# montaj_lora.net
KiCad netlist of a schematic drawn in EAGLE
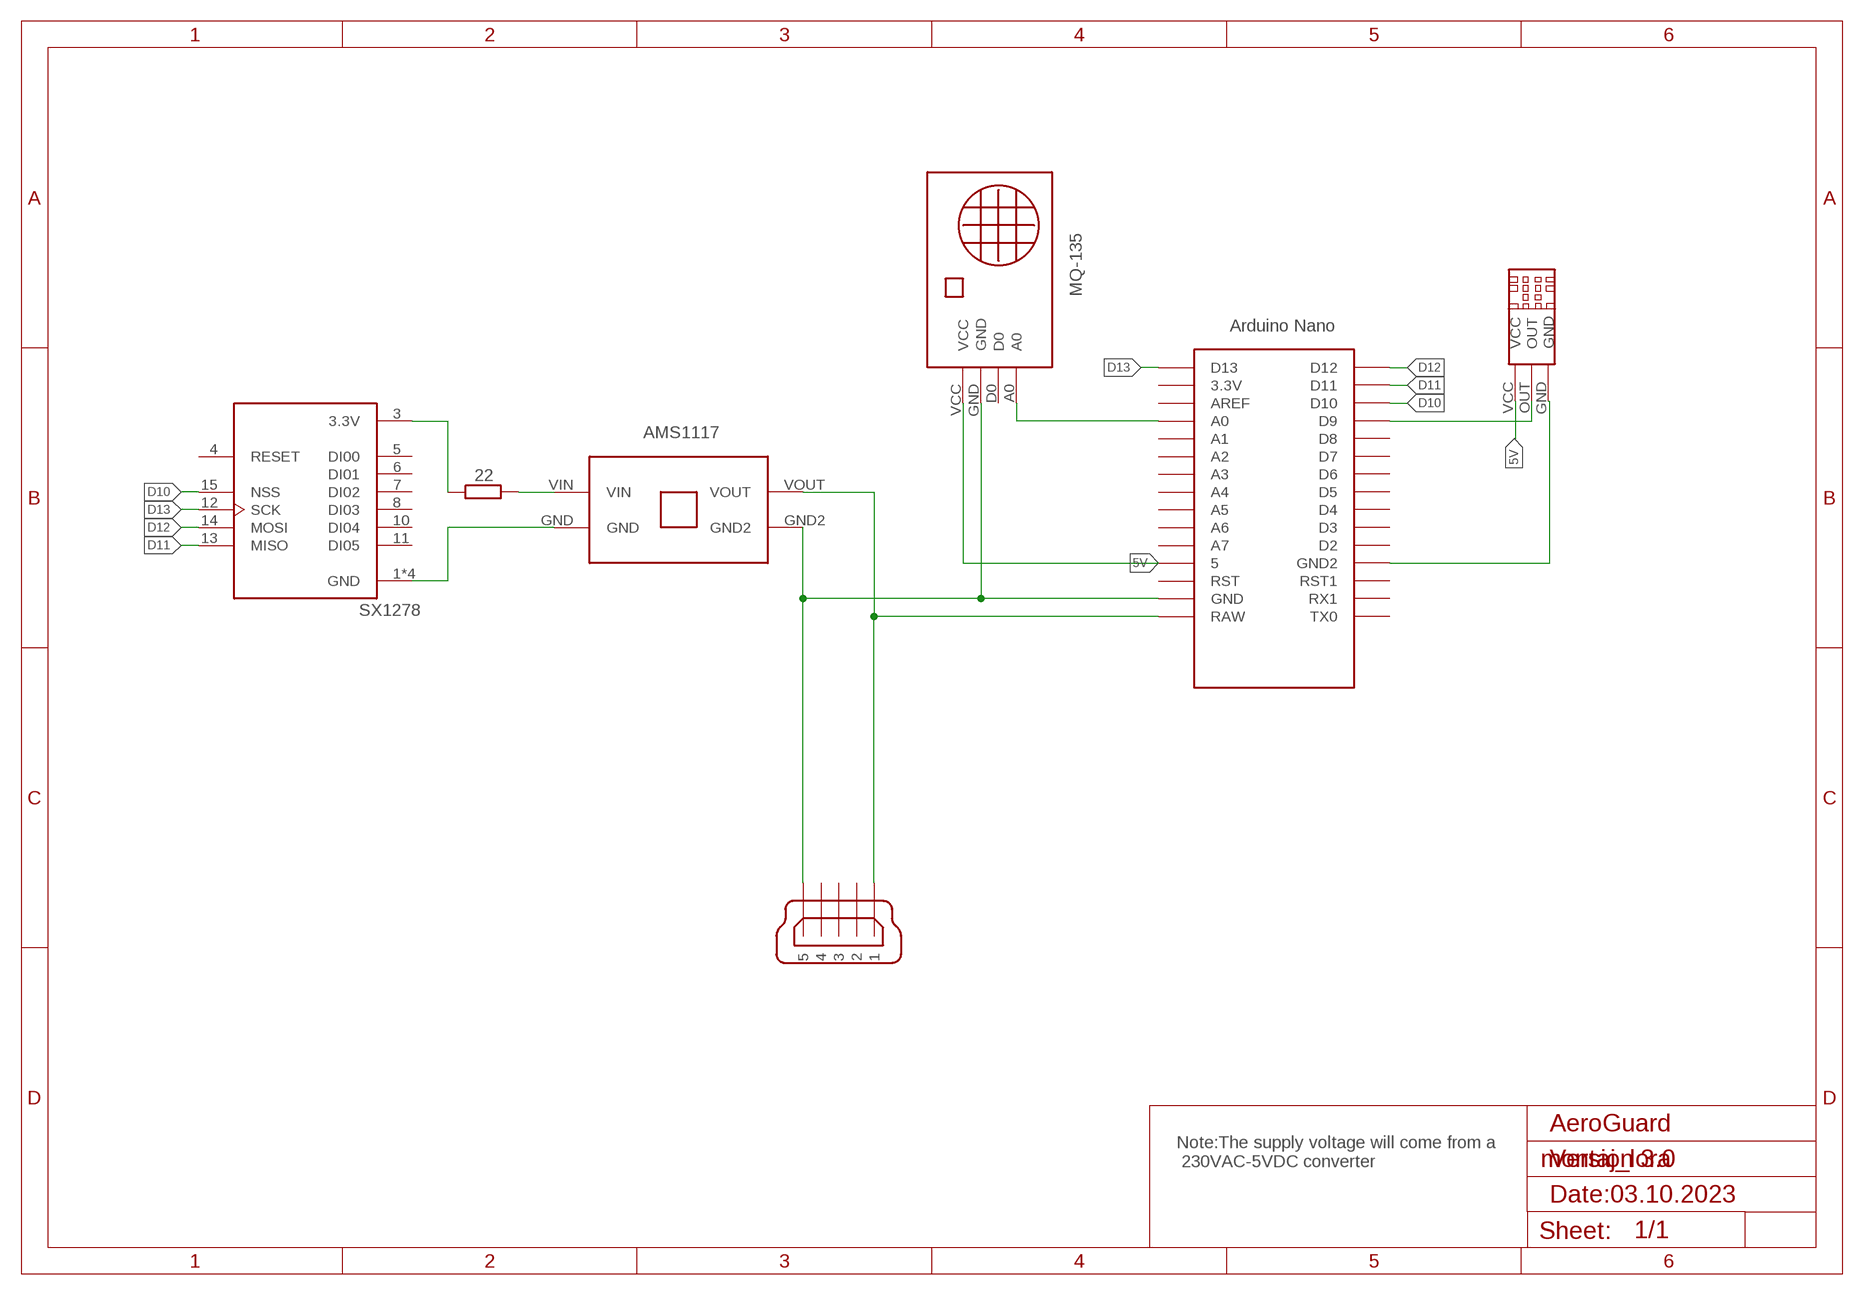
[diagram p0: schematic, sheet 1]

(export (version "E")
  (design (tool "Eeschema 10.0.6"))
  (components
    (comp (ref "22")
      (value "R-EU_0207/12")
      (footprint "eagle-import:0207_12")
      (libsource (lib "eagle-import") (part "R-EU_0207/12"))
    )
    (comp (ref "U$1")
      (value "NANO")
      (footprint "eagle-import:NANO")
      (libsource (lib "eagle-import") (part "NANO"))
    )
    (comp (ref "U$2")
      (value "DEV")
      (footprint "eagle-import:FOOT")
      (libsource (lib "eagle-import") (part "DEV"))
    )
    (comp (ref "U$3")
      (value "AMS1117")
      (footprint "eagle-import:AMS1117")
      (libsource (lib "eagle-import") (part "AMS1117"))
    )
    (comp (ref "U$4")
      (value "DHT11")
      (footprint "eagle-import:DHT11")
      (libsource (lib "eagle-import") (part "DHT11"))
    )
    (comp (ref "U1")
      (value "RA-02_LORA")
      (footprint "eagle-import:MODULE_RA-02_LORA")
      (fields (field (name "MF") "AI-Thinker") (field (name "MP") "Ra-02 LoRa"))
      (libsource (lib "eagle-import") (part "RA-02_LORA"))
    )
    (comp (ref "X1")
      (value "MINI-USB-SHIELD-UX60-MB-5S8")
      (footprint "eagle-import:UX60-MB-5S8")
      (libsource (lib "eagle-import") (part "MINI-USB-SHIELD-UX60-MB-5S8"))
    )
  )
  (nets
    (net (code "1") (name "5V") (class "Default")
      (node (ref "U$1") (pin "5V") (pinfunction "5_5V") (pintype "bidirectional"))
      (node (ref "U$2") (pin "VCC") (pinfunction "VCC_VCC") (pintype "bidirectional"))
    )
    (net (code "2") (name "D10") (class "Default")
      (node (ref "U$1") (pin "D10") (pinfunction "D10_D10") (pintype "bidirectional"))
      (node (ref "U1") (pin "15") (pinfunction "NSS_15") (pintype "input"))
    )
    (net (code "3") (name "D11") (class "Default")
      (node (ref "U$1") (pin "D11") (pinfunction "D11_D11") (pintype "bidirectional"))
      (node (ref "U1") (pin "13") (pinfunction "MISO_13") (pintype "output"))
    )
    (net (code "4") (name "D12") (class "Default")
      (node (ref "U$1") (pin "D12") (pinfunction "D12_D12") (pintype "bidirectional"))
      (node (ref "U1") (pin "14") (pinfunction "MOSI_14") (pintype "input"))
    )
    (net (code "5") (name "D13") (class "Default")
      (node (ref "U$1") (pin "D13") (pinfunction "D13_D13") (pintype "bidirectional"))
      (node (ref "U1") (pin "12") (pinfunction "SCK_12") (pintype "input"))
    )
    (net (code "6") (name "Net-(22-Pad2)") (class "Default")
      (node (ref "22") (pin "2") (pinfunction "2_2") (pintype "passive"))
      (node (ref "U$3") (pin "VIN") (pinfunction "VIN_VIN") (pintype "bidirectional"))
    )
    (net (code "7") (name "Net-(U$1-GND2)") (class "Default")
      (node (ref "U$1") (pin "GND1") (pinfunction "GND2_GND1") (pintype "bidirectional"))
      (node (ref "U$4") (pin "GND") (pinfunction "GND_GND") (pintype "bidirectional"))
    )
    (net (code "8") (name "Net-(U$1-PadA0)") (class "Default")
      (node (ref "U$1") (pin "A0") (pinfunction "A0_A0") (pintype "bidirectional"))
      (node (ref "U$2") (pin "A0") (pinfunction "A0_A0") (pintype "bidirectional"))
    )
    (net (code "9") (name "Net-(U$1-PadD9)") (class "Default")
      (node (ref "U$1") (pin "D9") (pinfunction "D9_D9") (pintype "bidirectional"))
      (node (ref "U$4") (pin "OUT") (pinfunction "OUT_OUT") (pintype "bidirectional"))
    )
    (net (code "10") (name "Net-(U$1-PadGND)") (class "Default")
      (node (ref "U$1") (pin "GND") (pinfunction "GND_GND") (pintype "bidirectional"))
      (node (ref "U$2") (pin "GND") (pinfunction "GND_GND") (pintype "bidirectional"))
      (node (ref "U$3") (pin "GND2") (pinfunction "GND2_GND2") (pintype "bidirectional"))
      (node (ref "X1") (pin "5") (pinfunction "5_5") (pintype "input"))
    )
    (net (code "11") (name "Net-(U$1-PadRAW)") (class "Default")
      (node (ref "U$1") (pin "RAW") (pinfunction "RAW_RAW") (pintype "bidirectional"))
      (node (ref "U$3") (pin "VOUT") (pinfunction "VOUT_VOUT") (pintype "bidirectional"))
      (node (ref "X1") (pin "1") (pinfunction "1_1") (pintype "input"))
    )
    (net (code "12") (name "Net-(U$3-PadGND)") (class "Default")
      (node (ref "U$3") (pin "GND") (pinfunction "GND_GND") (pintype "bidirectional"))
      (node (ref "U1") (pin "1") (pinfunction "GND_1") (pintype "power_in"))
      (node (ref "U1") (pin "16") (pinfunction "GND_16") (pintype "power_in"))
      (node (ref "U1") (pin "2") (pinfunction "GND_2") (pintype "power_in"))
      (node (ref "U1") (pin "9") (pinfunction "GND_9") (pintype "power_in"))
    )
    (net (code "13") (name "Net-(U1-3.3V)") (class "Default")
      (node (ref "22") (pin "1") (pinfunction "1_1") (pintype "passive"))
      (node (ref "U1") (pin "3") (pinfunction "3.3V_3") (pintype "power_in"))
    )
    (net (code "14") (name "unconnected-(U$1-Pad3.3V)") (class "Default")
      (node (ref "U$1") (pin "3.3V") (pinfunction "3.3V_3.3V") (pintype "bidirectional"))
    )
    (net (code "15") (name "unconnected-(U$1-PadA1)") (class "Default")
      (node (ref "U$1") (pin "A1") (pinfunction "A1_A1") (pintype "bidirectional"))
    )
    (net (code "16") (name "unconnected-(U$1-PadA2)") (class "Default")
      (node (ref "U$1") (pin "A2") (pinfunction "A2_A2") (pintype "bidirectional"))
    )
    (net (code "17") (name "unconnected-(U$1-PadA3)") (class "Default")
      (node (ref "U$1") (pin "A3") (pinfunction "A3_A3") (pintype "bidirectional"))
    )
    (net (code "18") (name "unconnected-(U$1-PadA4)") (class "Default")
      (node (ref "U$1") (pin "A4") (pinfunction "A4_A4") (pintype "bidirectional"))
    )
    (net (code "19") (name "unconnected-(U$1-PadA5)") (class "Default")
      (node (ref "U$1") (pin "A5") (pinfunction "A5_A5") (pintype "bidirectional"))
    )
    (net (code "20") (name "unconnected-(U$1-PadA6)") (class "Default")
      (node (ref "U$1") (pin "A6") (pinfunction "A6_A6") (pintype "bidirectional"))
    )
    (net (code "21") (name "unconnected-(U$1-PadA7)") (class "Default")
      (node (ref "U$1") (pin "A7") (pinfunction "A7_A7") (pintype "bidirectional"))
    )
    (net (code "22") (name "unconnected-(U$1-PadAREF)") (class "Default")
      (node (ref "U$1") (pin "AREF") (pinfunction "AREF_AREF") (pintype "bidirectional"))
    )
    (net (code "23") (name "unconnected-(U$1-PadD2)") (class "Default")
      (node (ref "U$1") (pin "D2") (pinfunction "D2_D2") (pintype "bidirectional"))
    )
    (net (code "24") (name "unconnected-(U$1-PadD3)") (class "Default")
      (node (ref "U$1") (pin "D3") (pinfunction "D3_D3") (pintype "bidirectional"))
    )
    (net (code "25") (name "unconnected-(U$1-PadD4)") (class "Default")
      (node (ref "U$1") (pin "D4") (pinfunction "D4_D4") (pintype "bidirectional"))
    )
    (net (code "26") (name "unconnected-(U$1-PadD5)") (class "Default")
      (node (ref "U$1") (pin "D5") (pinfunction "D5_D5") (pintype "bidirectional"))
    )
    (net (code "27") (name "unconnected-(U$1-PadD6)") (class "Default")
      (node (ref "U$1") (pin "D6") (pinfunction "D6_D6") (pintype "bidirectional"))
    )
    (net (code "28") (name "unconnected-(U$1-PadD7)") (class "Default")
      (node (ref "U$1") (pin "D7") (pinfunction "D7_D7") (pintype "bidirectional"))
    )
    (net (code "29") (name "unconnected-(U$1-PadD8)") (class "Default")
      (node (ref "U$1") (pin "D8") (pinfunction "D8_D8") (pintype "bidirectional"))
    )
    (net (code "30") (name "unconnected-(U$1-PadICSP1)") (class "Default")
      (node (ref "U$1") (pin "ICSP1") (pinfunction "ICSP1_ICSP1") (pintype "bidirectional"))
    )
    (net (code "31") (name "unconnected-(U$1-PadICSP2)") (class "Default")
      (node (ref "U$1") (pin "ICSP2") (pinfunction "ICSP2_ICSP2") (pintype "bidirectional"))
    )
    (net (code "32") (name "unconnected-(U$1-PadICSP3)") (class "Default")
      (node (ref "U$1") (pin "ICSP3") (pinfunction "ICSP3_ICSP3") (pintype "bidirectional"))
    )
    (net (code "33") (name "unconnected-(U$1-PadICSP4)") (class "Default")
      (node (ref "U$1") (pin "ICSP4") (pinfunction "ICSP4_ICSP4") (pintype "bidirectional"))
    )
    (net (code "34") (name "unconnected-(U$1-PadICSP5)") (class "Default")
      (node (ref "U$1") (pin "ICSP5") (pinfunction "ICSP5_ICSP5") (pintype "bidirectional"))
    )
    (net (code "35") (name "unconnected-(U$1-PadICSP6)") (class "Default")
      (node (ref "U$1") (pin "ICSP6") (pinfunction "ICSP6_ICSP6") (pintype "bidirectional"))
    )
    (net (code "36") (name "unconnected-(U$1-PadRST)") (class "Default")
      (node (ref "U$1") (pin "RST") (pinfunction "RST_RST") (pintype "bidirectional"))
    )
    (net (code "37") (name "unconnected-(U$1-PadRST1)") (class "Default")
      (node (ref "U$1") (pin "RST1") (pinfunction "RST1_RST1") (pintype "bidirectional"))
    )
    (net (code "38") (name "unconnected-(U$1-PadRX1)") (class "Default")
      (node (ref "U$1") (pin "RX1") (pinfunction "RX1_RX1") (pintype "bidirectional"))
    )
    (net (code "39") (name "unconnected-(U$1-PadTX0)") (class "Default")
      (node (ref "U$1") (pin "TX0") (pinfunction "TX0_TX0") (pintype "bidirectional"))
    )
    (net (code "40") (name "unconnected-(U$2-PadD0)") (class "Default")
      (node (ref "U$2") (pin "D0") (pinfunction "D0_D0") (pintype "bidirectional"))
    )
    (net (code "41") (name "unconnected-(U$4-PadVCC)") (class "Default")
      (node (ref "U$4") (pin "VCC") (pinfunction "VCC_VCC") (pintype "bidirectional"))
    )
    (net (code "42") (name "unconnected-(U1-DI00-Pad5)") (class "Default")
      (node (ref "U1") (pin "5") (pinfunction "DI00_5") (pintype "bidirectional"))
    )
    (net (code "43") (name "unconnected-(U1-DI01-Pad6)") (class "Default")
      (node (ref "U1") (pin "6") (pinfunction "DI01_6") (pintype "bidirectional"))
    )
    (net (code "44") (name "unconnected-(U1-DI02-Pad7)") (class "Default")
      (node (ref "U1") (pin "7") (pinfunction "DI02_7") (pintype "bidirectional"))
    )
    (net (code "45") (name "unconnected-(U1-DI03-Pad8)") (class "Default")
      (node (ref "U1") (pin "8") (pinfunction "DI03_8") (pintype "bidirectional"))
    )
    (net (code "46") (name "unconnected-(U1-DI04-Pad10)") (class "Default")
      (node (ref "U1") (pin "10") (pinfunction "DI04_10") (pintype "bidirectional"))
    )
    (net (code "47") (name "unconnected-(U1-DI05-Pad11)") (class "Default")
      (node (ref "U1") (pin "11") (pinfunction "DI05_11") (pintype "bidirectional"))
    )
    (net (code "48") (name "unconnected-(U1-RESET-Pad4)") (class "Default")
      (node (ref "U1") (pin "4") (pinfunction "RESET_4") (pintype "input"))
    )
    (net (code "49") (name "unconnected-(X1-Pad2)") (class "Default")
      (node (ref "X1") (pin "2") (pinfunction "2_2") (pintype "input"))
    )
    (net (code "50") (name "unconnected-(X1-Pad3)") (class "Default")
      (node (ref "X1") (pin "3") (pinfunction "3_3") (pintype "input"))
    )
    (net (code "51") (name "unconnected-(X1-Pad4)") (class "Default")
      (node (ref "X1") (pin "4") (pinfunction "4_4") (pintype "input"))
    )
  )
)
